# sensors.net
KiCad netlist of a schematic drawn in Altium Designer
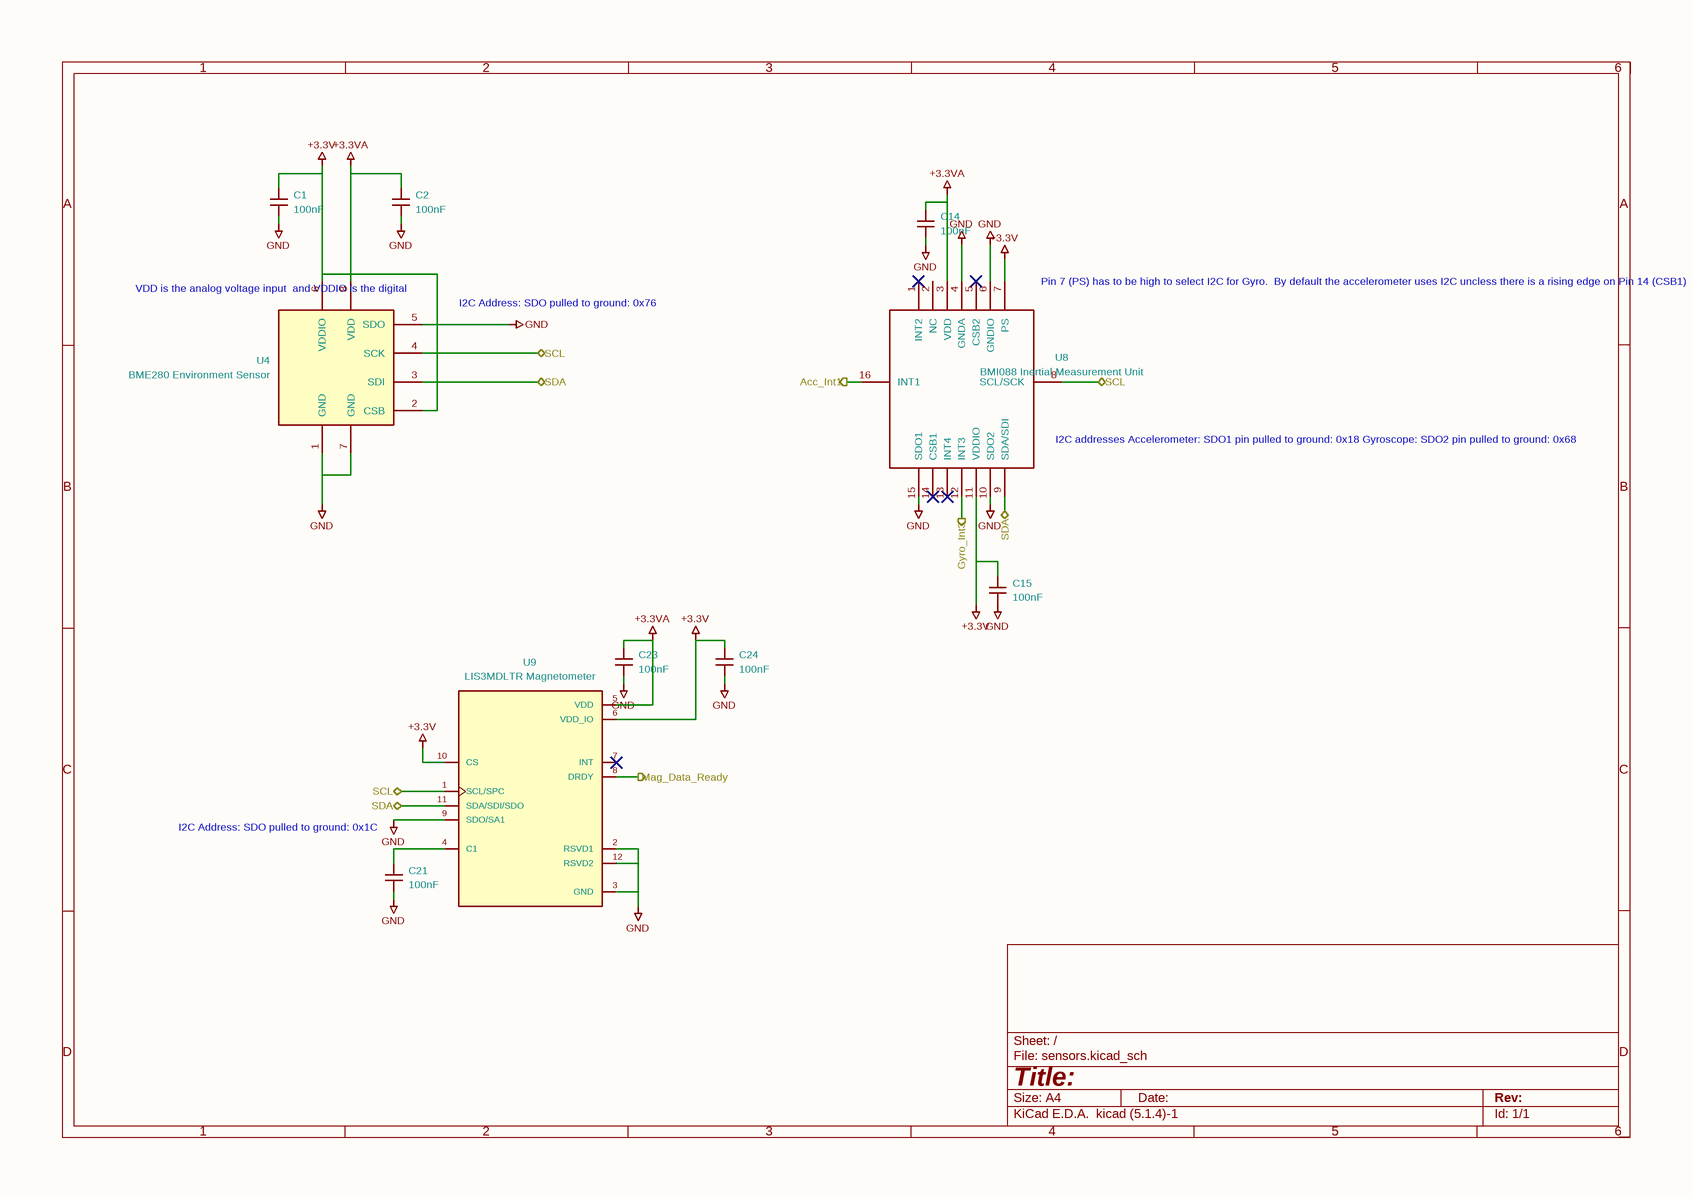
[diagram p0: sensors.SchDoc]

(export (version "E")
  (design (tool "Eeschema 10.0.6"))
  (components
    (comp (ref "C1") (value "100nF") (libsource (lib "Components") (part "C_0603")))
    (comp (ref "C2") (value "100nF") (libsource (lib "Components") (part "C_0603")))
    (comp (ref "C14") (value "100nF") (libsource (lib "Components") (part "C_0603")))
    (comp (ref "C15") (value "100nF") (libsource (lib "Components") (part "C_0603")))
    (comp (ref "C21") (value "100nF") (libsource (lib "Components") (part "C_0603")))
    (comp (ref "C23") (value "100nF") (libsource (lib "Components") (part "C_0603")))
    (comp (ref "C24") (value "100nF") (libsource (lib "Components") (part "C_0603")))
    (comp (ref "U4") (value "BME280 Environment Sensor") (libsource (lib "Sensor") (part "BME280")))
    (comp (ref "U8")
      (value "BMI088 Inertial Measurement Unit")
      (description "Inertial Measurement Unit Digital Output 2.5V/3.3V Automotive")
      (fields
        (field (name "MANUFACTURER_PART_NUMBER") "BMI088")
        (field (name "MOUSER PART NUMBER") "262-BMI088")
      )
      (libsource (lib "Components") (part "BMI088"))
    )
    (comp (ref "U9")
      (value "LIS3MDLTR Magnetometer")
      (description "LIS3MDL Series 3 Axis ±2/±8/±12/±16 g 3.6V High Performance Magnetometer LGA-12")
      (fields (field (name "MF") "STMicroelectronics") (field (name "MP") "LIS3MDLTR"))
      (libsource (lib "Components") (part "LIS3MDLTR"))
    )
  )
  (nets
    (net (code "1") (name "+3.3V") (class "Default")
      (node (ref "C1") (pin "1") (pinfunction "1_1") (pintype "passive"))
      (node (ref "C15") (pin "1") (pinfunction "1_1") (pintype "passive"))
      (node (ref "C24") (pin "1") (pinfunction "1_1") (pintype "passive"))
      (node (ref "U4") (pin "2") (pinfunction "CSB_2") (pintype "passive"))
      (node (ref "U4") (pin "6") (pinfunction "VDDIO_6") (pintype "passive"))
      (node (ref "U8") (pin "11") (pinfunction "VDDIO_11") (pintype "passive"))
      (node (ref "U8") (pin "7") (pinfunction "PS_7") (pintype "passive"))
      (node (ref "U9") (pin "10") (pinfunction "CS_10") (pintype "passive"))
      (node (ref "U9") (pin "6") (pinfunction "VDD_IO_6") (pintype "passive"))
    )
    (net (code "2") (name "+3.3VA") (class "Default")
      (node (ref "C14") (pin "1") (pinfunction "1_1") (pintype "passive"))
      (node (ref "C2") (pin "1") (pinfunction "1_1") (pintype "passive"))
      (node (ref "C23") (pin "1") (pinfunction "1_1") (pintype "passive"))
      (node (ref "U4") (pin "8") (pinfunction "VDD_8") (pintype "passive"))
      (node (ref "U8") (pin "3") (pinfunction "VDD_3") (pintype "passive"))
      (node (ref "U9") (pin "5") (pinfunction "VDD_5") (pintype "passive"))
    )
    (net (code "3") (name "/Acc_Int1") (class "Default")
      (node (ref "U8") (pin "16") (pinfunction "INT1_16") (pintype "passive"))
    )
    (net (code "4") (name "/Gyro_Int3") (class "Default")
      (node (ref "U8") (pin "12") (pinfunction "INT3_12") (pintype "passive"))
    )
    (net (code "5") (name "/Mag_Data_Ready") (class "Default")
      (node (ref "U9") (pin "8") (pinfunction "DRDY_8") (pintype "passive"))
    )
    (net (code "6") (name "/SCL") (class "Default")
      (node (ref "U4") (pin "4") (pinfunction "SCK_4") (pintype "passive"))
      (node (ref "U8") (pin "8") (pinfunction "SCL/SCK_8") (pintype "passive"))
      (node (ref "U9") (pin "1") (pinfunction "SCL/SPC_1") (pintype "passive"))
    )
    (net (code "7") (name "/SDA") (class "Default")
      (node (ref "U4") (pin "3") (pinfunction "SDI_3") (pintype "passive"))
      (node (ref "U8") (pin "9") (pinfunction "SDA/SDI_9") (pintype "passive"))
      (node (ref "U9") (pin "11") (pinfunction "SDA/SDI/SDO_11") (pintype "passive"))
    )
    (net (code "8") (name "GND") (class "Default")
      (node (ref "C1") (pin "2") (pinfunction "2_2") (pintype "passive"))
      (node (ref "C14") (pin "2") (pinfunction "2_2") (pintype "passive"))
      (node (ref "C15") (pin "2") (pinfunction "2_2") (pintype "passive"))
      (node (ref "C2") (pin "2") (pinfunction "2_2") (pintype "passive"))
      (node (ref "C21") (pin "2") (pinfunction "2_2") (pintype "passive"))
      (node (ref "C23") (pin "2") (pinfunction "2_2") (pintype "passive"))
      (node (ref "C24") (pin "2") (pinfunction "2_2") (pintype "passive"))
      (node (ref "U4") (pin "1") (pinfunction "GND_1") (pintype "passive"))
      (node (ref "U4") (pin "5") (pinfunction "SDO_5") (pintype "passive"))
      (node (ref "U4") (pin "7") (pinfunction "GND_7") (pintype "passive"))
      (node (ref "U8") (pin "10") (pinfunction "SDO2_10") (pintype "passive"))
      (node (ref "U8") (pin "15") (pinfunction "SDO1_15") (pintype "passive"))
      (node (ref "U8") (pin "4") (pinfunction "GNDA_4") (pintype "passive"))
      (node (ref "U8") (pin "6") (pinfunction "GNDIO_6") (pintype "passive"))
      (node (ref "U9") (pin "12") (pinfunction "RSVD2_12") (pintype "passive"))
      (node (ref "U9") (pin "2") (pinfunction "RSVD1_2") (pintype "passive"))
      (node (ref "U9") (pin "3") (pinfunction "GND_3") (pintype "passive"))
      (node (ref "U9") (pin "9") (pinfunction "SDO/SA1_9") (pintype "passive"))
    )
    (net (code "9") (name "Net-(U9-C1)") (class "Default")
      (node (ref "C21") (pin "1") (pinfunction "1_1") (pintype "passive"))
      (node (ref "U9") (pin "4") (pinfunction "C1_4") (pintype "passive"))
    )
    (net (code "10") (name "unconnected-(U8-CSB1-Pad14)") (class "Default")
      (node (ref "U8") (pin "14") (pinfunction "CSB1_14") (pintype "passive+no_connect"))
    )
    (net (code "11") (name "unconnected-(U8-CSB2-Pad5)") (class "Default")
      (node (ref "U8") (pin "5") (pinfunction "CSB2_5") (pintype "passive+no_connect"))
    )
    (net (code "12") (name "unconnected-(U8-INT2-Pad1)") (class "Default")
      (node (ref "U8") (pin "1") (pinfunction "INT2_1") (pintype "passive+no_connect"))
    )
    (net (code "13") (name "unconnected-(U8-INT4-Pad13)") (class "Default")
      (node (ref "U8") (pin "13") (pinfunction "INT4_13") (pintype "passive+no_connect"))
    )
    (net (code "14") (name "unconnected-(U8-NC-Pad2)") (class "Default")
      (node (ref "U8") (pin "2") (pinfunction "NC_2") (pintype "passive"))
    )
    (net (code "15") (name "unconnected-(U9-INT-Pad7)") (class "Default")
      (node (ref "U9") (pin "7") (pinfunction "INT_7") (pintype "passive+no_connect"))
    )
  )
)
